# Super-Regenerative-VHF-2Transistor-RickA.net
KiCad netlist of a schematic drawn in EAGLE
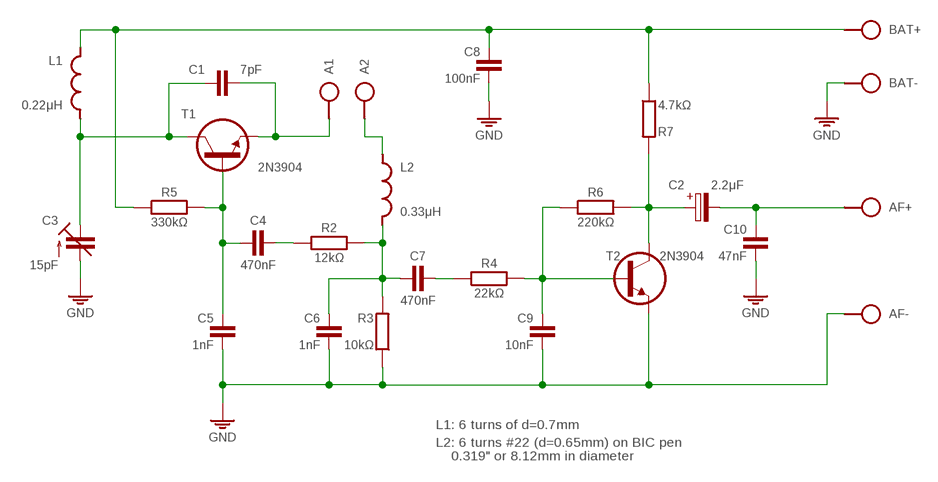
[diagram p0: schematic, sheet 1]

(export (version "E")
  (design (tool "Eeschema 10.0.6"))
  (components
    (comp (ref "A1")
      (value "SPAD")
      (footprint "eagle-import:SPAD")
      (libsource (lib "eagle-import") (part "SPAD"))
    )
    (comp (ref "A2")
      (value "SPAD")
      (footprint "eagle-import:SPAD")
      (libsource (lib "eagle-import") (part "SPAD"))
    )
    (comp (ref "AF+")
      (value "SPAD")
      (footprint "eagle-import:SPAD")
      (libsource (lib "eagle-import") (part "SPAD"))
    )
    (comp (ref "AF-")
      (value "SPAD")
      (footprint "eagle-import:SPAD")
      (libsource (lib "eagle-import") (part "SPAD"))
    )
    (comp (ref "BAT+")
      (value "SPAD")
      (footprint "eagle-import:SPAD")
      (libsource (lib "eagle-import") (part "SPAD"))
    )
    (comp (ref "BAT-")
      (value "SPAD")
      (footprint "eagle-import:SPAD")
      (libsource (lib "eagle-import") (part "SPAD"))
    )
    (comp (ref "C1")
      (value "7pF")
      (footprint "eagle-import:C050-020X036")
      (libsource (lib "eagle-import") (part "C050-020X036"))
    )
    (comp (ref "C2")
      (value "2.2μF")
      (footprint "eagle-import:E2,5-3")
      (libsource (lib "eagle-import") (part "CPOLE2,5-3"))
    )
    (comp (ref "C3")
      (value "15pF")
      (footprint "eagle-import:TRIM-2222-808")
      (libsource (lib "eagle-import") (part "C-TR-PH201272222-808-2PINB"))
    )
    (comp (ref "C4")
      (value "470nF")
      (footprint "eagle-import:C050-024X044_V")
      (libsource (lib "eagle-import") (part "C050-024X044/V"))
    )
    (comp (ref "C5")
      (value "1nF")
      (footprint "eagle-import:C025-020X036")
      (libsource (lib "eagle-import") (part "C025-020X036"))
    )
    (comp (ref "C6")
      (value "1nF")
      (footprint "eagle-import:C025-020X036")
      (libsource (lib "eagle-import") (part "C025-020X036"))
    )
    (comp (ref "C7")
      (value "470nF")
      (footprint "eagle-import:C050-024X044_V")
      (libsource (lib "eagle-import") (part "C050-024X044/V"))
    )
    (comp (ref "C8")
      (value "100nF")
      (footprint "eagle-import:C050-020X044")
      (libsource (lib "eagle-import") (part "C050-020X044"))
    )
    (comp (ref "C9")
      (value "10nF")
      (footprint "eagle-import:C025-015X024")
      (libsource (lib "eagle-import") (part "C025-015X024"))
    )
    (comp (ref "C10")
      (value "47nF")
      (footprint "eagle-import:C050-020X036_V")
      (libsource (lib "eagle-import") (part "C050-020X036/V"))
    )
    (comp (ref "L1")
      (value "0.22μH")
      (footprint "eagle-import:L-04-5_6V")
      (libsource (lib "eagle-import") (part "L-SHORT04-5/5V"))
    )
    (comp (ref "L2")
      (value "0.33μH")
      (footprint "eagle-import:L-08-5_8")
      (libsource (lib "eagle-import") (part "L-SHORTL-08-5/8"))
    )
    (comp (ref "R2")
      (value "12kΩ")
      (footprint "eagle-import:0202_7")
      (libsource (lib "eagle-import") (part "R-H0202/7"))
    )
    (comp (ref "R3")
      (value "10kΩ")
      (footprint "eagle-import:0202_5-V")
      (libsource (lib "eagle-import") (part "R0202/5-V"))
    )
    (comp (ref "R4")
      (value "22kΩ")
      (footprint "eagle-import:0202_7-V")
      (libsource (lib "eagle-import") (part "R-H0202/7-V"))
    )
    (comp (ref "R5")
      (value "330kΩ")
      (footprint "eagle-import:0202_7")
      (libsource (lib "eagle-import") (part "R-H0202/7"))
    )
    (comp (ref "R6")
      (value "220kΩ")
      (footprint "eagle-import:0202_7-V")
      (libsource (lib "eagle-import") (part "R-H0202/7-V"))
    )
    (comp (ref "R7")
      (value "4.7kΩ")
      (footprint "eagle-import:0202_7-V")
      (libsource (lib "eagle-import") (part "R0202/7-V"))
    )
    (comp (ref "T1")
      (value "2N3904")
      (footprint "eagle-import:TO92")
      (libsource (lib "eagle-import") (part "2N3904"))
    )
    (comp (ref "T2")
      (value "2N3904")
      (footprint "eagle-import:TO92")
      (libsource (lib "eagle-import") (part "2N3904"))
    )
  )
  (nets
    (net (code "1") (name "GND") (class "Default")
      (node (ref "AF-") (pin "1") (pinfunction "P$1_1") (pintype "passive"))
      (node (ref "BAT-") (pin "1") (pinfunction "P$1_1") (pintype "passive"))
      (node (ref "C10") (pin "2") (pinfunction "2_2") (pintype "passive"))
      (node (ref "C3") (pin "2") (pinfunction "A_2") (pintype "passive"))
      (node (ref "C5") (pin "2") (pinfunction "2_2") (pintype "passive"))
      (node (ref "C6") (pin "2") (pinfunction "2_2") (pintype "passive"))
      (node (ref "C8") (pin "2") (pinfunction "2_2") (pintype "passive"))
      (node (ref "C9") (pin "2") (pinfunction "2_2") (pintype "passive"))
      (node (ref "R3") (pin "1") (pinfunction "2_1") (pintype "passive"))
      (node (ref "T2") (pin "1") (pinfunction "E_1") (pintype "passive"))
    )
    (net (code "2") (name "Net-(A1-P$1)") (class "Default")
      (node (ref "A1") (pin "1") (pinfunction "P$1_1") (pintype "passive"))
      (node (ref "C1") (pin "1") (pinfunction "1_1") (pintype "passive"))
      (node (ref "T1") (pin "1") (pinfunction "E_1") (pintype "passive"))
    )
    (net (code "3") (name "Net-(A2-P$1)") (class "Default")
      (node (ref "A2") (pin "1") (pinfunction "P$1_1") (pintype "passive"))
      (node (ref "L2") (pin "2") (pinfunction "2_2") (pintype "passive"))
    )
    (net (code "4") (name "Net-(AF+-P$1)") (class "Default")
      (node (ref "AF+") (pin "1") (pinfunction "P$1_1") (pintype "passive"))
      (node (ref "C10") (pin "1") (pinfunction "1_1") (pintype "passive"))
      (node (ref "C2") (pin "-") (pinfunction "-_-") (pintype "passive"))
    )
    (net (code "5") (name "Net-(BAT+-P$1)") (class "Default")
      (node (ref "BAT+") (pin "1") (pinfunction "P$1_1") (pintype "passive"))
      (node (ref "C8") (pin "1") (pinfunction "1_1") (pintype "passive"))
      (node (ref "L1") (pin "1") (pinfunction "2_1") (pintype "passive"))
      (node (ref "R5") (pin "1") (pinfunction "1_1") (pintype "passive"))
      (node (ref "R7") (pin "1") (pinfunction "2_1") (pintype "passive"))
    )
    (net (code "6") (name "Net-(C3-E)") (class "Default")
      (node (ref "C1") (pin "2") (pinfunction "2_2") (pintype "passive"))
      (node (ref "C3") (pin "3") (pinfunction "E_3") (pintype "passive"))
      (node (ref "L1") (pin "2") (pinfunction "1_2") (pintype "passive"))
      (node (ref "T1") (pin "3") (pinfunction "C_3") (pintype "passive"))
    )
    (net (code "7") (name "Net-(C4-Pad1)") (class "Default")
      (node (ref "C4") (pin "1") (pinfunction "1_1") (pintype "passive"))
      (node (ref "R2") (pin "1") (pinfunction "1_1") (pintype "passive"))
    )
    (net (code "8") (name "Net-(C7-Pad1)") (class "Default")
      (node (ref "C7") (pin "1") (pinfunction "1_1") (pintype "passive"))
      (node (ref "R4") (pin "1") (pinfunction "1_1") (pintype "passive"))
    )
    (net (code "9") (name "Net-(R3-1)") (class "Default")
      (node (ref "C6") (pin "1") (pinfunction "1_1") (pintype "passive"))
      (node (ref "C7") (pin "2") (pinfunction "2_2") (pintype "passive"))
      (node (ref "L2") (pin "1") (pinfunction "1_1") (pintype "passive"))
      (node (ref "R2") (pin "2") (pinfunction "2_2") (pintype "passive"))
      (node (ref "R3") (pin "2") (pinfunction "1_2") (pintype "passive"))
    )
    (net (code "10") (name "Net-(R7-1)") (class "Default")
      (node (ref "C2") (pin "+") (pinfunction "+_+") (pintype "passive"))
      (node (ref "R6") (pin "2") (pinfunction "2_2") (pintype "passive"))
      (node (ref "R7") (pin "2") (pinfunction "1_2") (pintype "passive"))
      (node (ref "T2") (pin "3") (pinfunction "C_3") (pintype "passive"))
    )
    (net (code "11") (name "Net-(T1-B)") (class "Default")
      (node (ref "C4") (pin "2") (pinfunction "2_2") (pintype "passive"))
      (node (ref "C5") (pin "1") (pinfunction "1_1") (pintype "passive"))
      (node (ref "R5") (pin "2") (pinfunction "2_2") (pintype "passive"))
      (node (ref "T1") (pin "2") (pinfunction "B_2") (pintype "passive"))
    )
    (net (code "12") (name "Net-(T2-B)") (class "Default")
      (node (ref "C9") (pin "1") (pinfunction "1_1") (pintype "passive"))
      (node (ref "R4") (pin "2") (pinfunction "2_2") (pintype "passive"))
      (node (ref "R6") (pin "1") (pinfunction "1_1") (pintype "passive"))
      (node (ref "T2") (pin "2") (pinfunction "B_2") (pintype "passive"))
    )
  )
)
